# 32_ch_sample_and_hold_v2.net
KiCad netlist of a schematic drawn in EAGLE
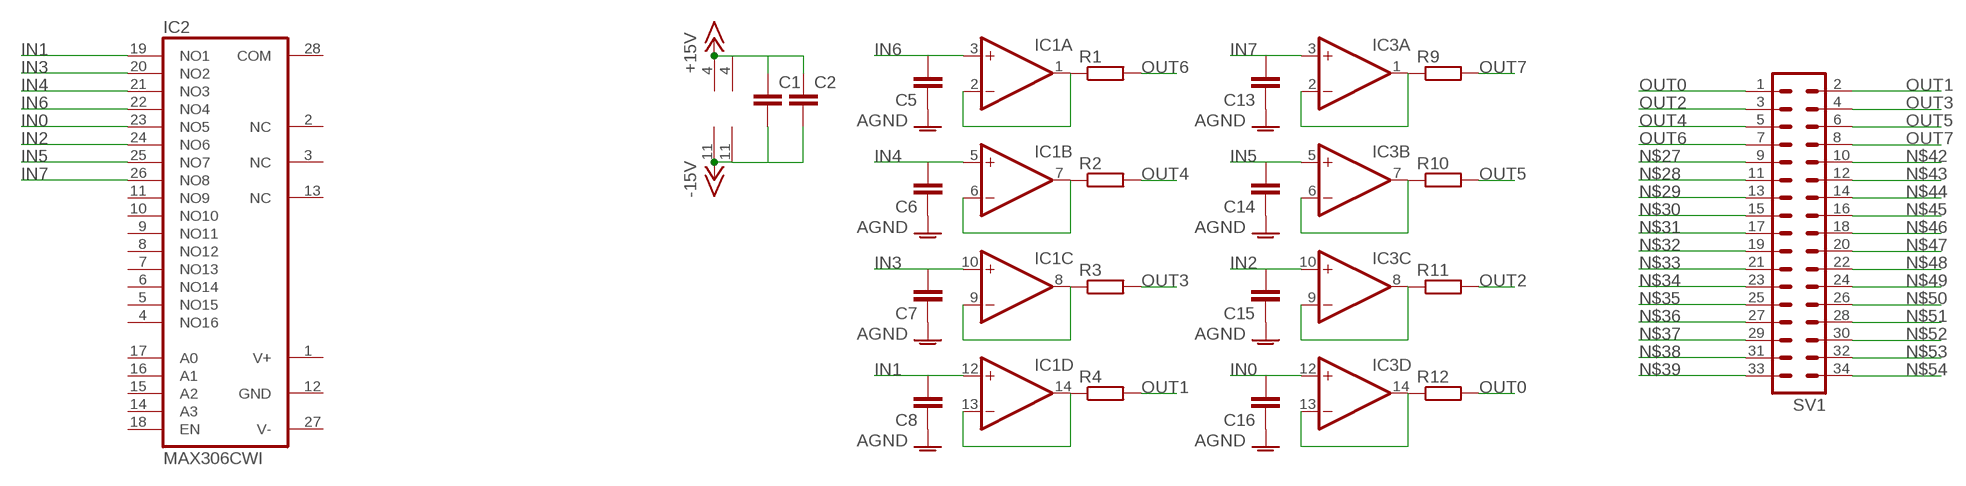
[diagram p0: schematic, sheet 1]

(export (version "E")
  (design (tool "Eeschema 10.0.6"))
  (components
    (comp (ref "C1")
      (value "C-EUC0603")
      (footprint "eagle-import:C0603")
      (libsource (lib "eagle-import") (part "C-EUC0603"))
    )
    (comp (ref "C2")
      (value "C-EUC0603")
      (footprint "eagle-import:C0603")
      (libsource (lib "eagle-import") (part "C-EUC0603"))
    )
    (comp (ref "C5")
      (value "C-EUC1206")
      (footprint "eagle-import:C1206")
      (libsource (lib "eagle-import") (part "C-EUC1206"))
    )
    (comp (ref "C6")
      (value "C-EUC1206")
      (footprint "eagle-import:C1206")
      (libsource (lib "eagle-import") (part "C-EUC1206"))
    )
    (comp (ref "C7")
      (value "C-EUC1206")
      (footprint "eagle-import:C1206")
      (libsource (lib "eagle-import") (part "C-EUC1206"))
    )
    (comp (ref "C8")
      (value "C-EUC1206")
      (footprint "eagle-import:C1206")
      (libsource (lib "eagle-import") (part "C-EUC1206"))
    )
    (comp (ref "C13")
      (value "C-EUC1206")
      (footprint "eagle-import:C1206")
      (libsource (lib "eagle-import") (part "C-EUC1206"))
    )
    (comp (ref "C14")
      (value "C-EUC1206")
      (footprint "eagle-import:C1206")
      (libsource (lib "eagle-import") (part "C-EUC1206"))
    )
    (comp (ref "C15")
      (value "C-EUC1206")
      (footprint "eagle-import:C1206")
      (libsource (lib "eagle-import") (part "C-EUC1206"))
    )
    (comp (ref "C16")
      (value "C-EUC1206")
      (footprint "eagle-import:C1206")
      (libsource (lib "eagle-import") (part "C-EUC1206"))
    )
    (comp (ref "IC1")
      (value "TL074D")
      (footprint "eagle-import:SO14")
      (libsource (lib "eagle-import") (part "TL074D"))
    )
    (comp (ref "IC2")
      (value "MAX306CWI")
      (footprint "eagle-import:SO28L")
      (fields (field (name "MF") "MAXIM"))
      (libsource (lib "eagle-import") (part "MAX306CWI"))
    )
    (comp (ref "IC3")
      (value "TL074D")
      (footprint "eagle-import:SO14")
      (libsource (lib "eagle-import") (part "TL074D"))
    )
    (comp (ref "R1")
      (value "R-EU_R0603")
      (footprint "eagle-import:R0603")
      (libsource (lib "eagle-import") (part "R-EU_R0603"))
    )
    (comp (ref "R2")
      (value "R-EU_R0603")
      (footprint "eagle-import:R0603")
      (libsource (lib "eagle-import") (part "R-EU_R0603"))
    )
    (comp (ref "R3")
      (value "R-EU_R0603")
      (footprint "eagle-import:R0603")
      (libsource (lib "eagle-import") (part "R-EU_R0603"))
    )
    (comp (ref "R4")
      (value "R-EU_R0603")
      (footprint "eagle-import:R0603")
      (libsource (lib "eagle-import") (part "R-EU_R0603"))
    )
    (comp (ref "R9")
      (value "R-EU_R0603")
      (footprint "eagle-import:R0603")
      (libsource (lib "eagle-import") (part "R-EU_R0603"))
    )
    (comp (ref "R10")
      (value "R-EU_R0603")
      (footprint "eagle-import:R0603")
      (libsource (lib "eagle-import") (part "R-EU_R0603"))
    )
    (comp (ref "R11")
      (value "R-EU_R0603")
      (footprint "eagle-import:R0603")
      (libsource (lib "eagle-import") (part "R-EU_R0603"))
    )
    (comp (ref "R12")
      (value "R-EU_R0603")
      (footprint "eagle-import:R0603")
      (libsource (lib "eagle-import") (part "R-EU_R0603"))
    )
    (comp (ref "SV1")
      (value "MA17-2")
      (footprint "eagle-import:MA17-2")
      (libsource (lib "eagle-import") (part "MA17-2"))
    )
  )
  (nets
    (net (code "1") (name "+15V") (class "Default")
      (node (ref "C1") (pin "1") (pinfunction "1_1") (pintype "passive"))
      (node (ref "C2") (pin "1") (pinfunction "1_1") (pintype "passive"))
      (node (ref "IC1") (pin "4") (pinfunction "V+_4") (pintype "power_in"))
      (node (ref "IC3") (pin "4") (pinfunction "V+_4") (pintype "power_in"))
    )
    (net (code "2") (name "-15V") (class "Default")
      (node (ref "C1") (pin "2") (pinfunction "2_2") (pintype "passive"))
      (node (ref "C2") (pin "2") (pinfunction "2_2") (pintype "passive"))
      (node (ref "IC1") (pin "11") (pinfunction "V-_11") (pintype "power_in"))
      (node (ref "IC3") (pin "11") (pinfunction "V-_11") (pintype "power_in"))
    )
    (net (code "3") (name "/GND") (class "Default")
      (node (ref "IC2") (pin "12") (pinfunction "GND_12") (pintype "power_in"))
    )
    (net (code "4") (name "/IN0") (class "Default")
      (node (ref "C16") (pin "2") (pinfunction "2_2") (pintype "passive"))
      (node (ref "IC2") (pin "23") (pinfunction "NO5_23") (pintype "passive"))
      (node (ref "IC3") (pin "12") (pinfunction "+IN_12") (pintype "input"))
    )
    (net (code "5") (name "/IN1") (class "Default")
      (node (ref "C8") (pin "2") (pinfunction "2_2") (pintype "passive"))
      (node (ref "IC1") (pin "12") (pinfunction "+IN_12") (pintype "input"))
      (node (ref "IC2") (pin "19") (pinfunction "NO1_19") (pintype "passive"))
    )
    (net (code "6") (name "/IN2") (class "Default")
      (node (ref "C15") (pin "2") (pinfunction "2_2") (pintype "passive"))
      (node (ref "IC2") (pin "24") (pinfunction "NO6_24") (pintype "passive"))
      (node (ref "IC3") (pin "10") (pinfunction "+IN_10") (pintype "input"))
    )
    (net (code "7") (name "/IN3") (class "Default")
      (node (ref "C7") (pin "2") (pinfunction "2_2") (pintype "passive"))
      (node (ref "IC1") (pin "10") (pinfunction "+IN_10") (pintype "input"))
      (node (ref "IC2") (pin "20") (pinfunction "NO2_20") (pintype "passive"))
    )
    (net (code "8") (name "/IN4") (class "Default")
      (node (ref "C6") (pin "2") (pinfunction "2_2") (pintype "passive"))
      (node (ref "IC1") (pin "5") (pinfunction "+IN_5") (pintype "input"))
      (node (ref "IC2") (pin "21") (pinfunction "NO3_21") (pintype "passive"))
    )
    (net (code "9") (name "/IN5") (class "Default")
      (node (ref "C14") (pin "2") (pinfunction "2_2") (pintype "passive"))
      (node (ref "IC2") (pin "25") (pinfunction "NO7_25") (pintype "passive"))
      (node (ref "IC3") (pin "5") (pinfunction "+IN_5") (pintype "input"))
    )
    (net (code "10") (name "/IN6") (class "Default")
      (node (ref "C5") (pin "2") (pinfunction "2_2") (pintype "passive"))
      (node (ref "IC1") (pin "3") (pinfunction "+IN_3") (pintype "input"))
      (node (ref "IC2") (pin "22") (pinfunction "NO4_22") (pintype "passive"))
    )
    (net (code "11") (name "/IN7") (class "Default")
      (node (ref "C13") (pin "2") (pinfunction "2_2") (pintype "passive"))
      (node (ref "IC2") (pin "26") (pinfunction "NO8_26") (pintype "passive"))
      (node (ref "IC3") (pin "3") (pinfunction "+IN_3") (pintype "input"))
    )
    (net (code "12") (name "/N$27") (class "Default")
      (node (ref "SV1") (pin "9") (pinfunction "9_9") (pintype "passive"))
    )
    (net (code "13") (name "/N$28") (class "Default")
      (node (ref "SV1") (pin "11") (pinfunction "11_11") (pintype "passive"))
    )
    (net (code "14") (name "/N$29") (class "Default")
      (node (ref "SV1") (pin "13") (pinfunction "13_13") (pintype "passive"))
    )
    (net (code "15") (name "/N$30") (class "Default")
      (node (ref "SV1") (pin "15") (pinfunction "15_15") (pintype "passive"))
    )
    (net (code "16") (name "/N$31") (class "Default")
      (node (ref "SV1") (pin "17") (pinfunction "17_17") (pintype "passive"))
    )
    (net (code "17") (name "/N$32") (class "Default")
      (node (ref "SV1") (pin "19") (pinfunction "19_19") (pintype "passive"))
    )
    (net (code "18") (name "/N$33") (class "Default")
      (node (ref "SV1") (pin "21") (pinfunction "21_21") (pintype "passive"))
    )
    (net (code "19") (name "/N$34") (class "Default")
      (node (ref "SV1") (pin "23") (pinfunction "23_23") (pintype "passive"))
    )
    (net (code "20") (name "/N$35") (class "Default")
      (node (ref "SV1") (pin "25") (pinfunction "25_25") (pintype "passive"))
    )
    (net (code "21") (name "/N$36") (class "Default")
      (node (ref "SV1") (pin "27") (pinfunction "27_27") (pintype "passive"))
    )
    (net (code "22") (name "/N$37") (class "Default")
      (node (ref "SV1") (pin "29") (pinfunction "29_29") (pintype "passive"))
    )
    (net (code "23") (name "/N$38") (class "Default")
      (node (ref "SV1") (pin "31") (pinfunction "31_31") (pintype "passive"))
    )
    (net (code "24") (name "/N$39") (class "Default")
      (node (ref "SV1") (pin "33") (pinfunction "33_33") (pintype "passive"))
    )
    (net (code "25") (name "/N$42") (class "Default")
      (node (ref "SV1") (pin "10") (pinfunction "10_10") (pintype "passive"))
    )
    (net (code "26") (name "/N$43") (class "Default")
      (node (ref "SV1") (pin "12") (pinfunction "12_12") (pintype "passive"))
    )
    (net (code "27") (name "/N$44") (class "Default")
      (node (ref "SV1") (pin "14") (pinfunction "14_14") (pintype "passive"))
    )
    (net (code "28") (name "/N$45") (class "Default")
      (node (ref "SV1") (pin "16") (pinfunction "16_16") (pintype "passive"))
    )
    (net (code "29") (name "/N$46") (class "Default")
      (node (ref "SV1") (pin "18") (pinfunction "18_18") (pintype "passive"))
    )
    (net (code "30") (name "/N$47") (class "Default")
      (node (ref "SV1") (pin "20") (pinfunction "20_20") (pintype "passive"))
    )
    (net (code "31") (name "/N$48") (class "Default")
      (node (ref "SV1") (pin "22") (pinfunction "22_22") (pintype "passive"))
    )
    (net (code "32") (name "/N$49") (class "Default")
      (node (ref "SV1") (pin "24") (pinfunction "24_24") (pintype "passive"))
    )
    (net (code "33") (name "/N$50") (class "Default")
      (node (ref "SV1") (pin "26") (pinfunction "26_26") (pintype "passive"))
    )
    (net (code "34") (name "/N$51") (class "Default")
      (node (ref "SV1") (pin "28") (pinfunction "28_28") (pintype "passive"))
    )
    (net (code "35") (name "/N$52") (class "Default")
      (node (ref "SV1") (pin "30") (pinfunction "30_30") (pintype "passive"))
    )
    (net (code "36") (name "/N$53") (class "Default")
      (node (ref "SV1") (pin "32") (pinfunction "32_32") (pintype "passive"))
    )
    (net (code "37") (name "/N$54") (class "Default")
      (node (ref "SV1") (pin "34") (pinfunction "34_34") (pintype "passive"))
    )
    (net (code "38") (name "/OUT0") (class "Default")
      (node (ref "R12") (pin "2") (pinfunction "2_2") (pintype "passive"))
      (node (ref "SV1") (pin "1") (pinfunction "1_1") (pintype "passive"))
    )
    (net (code "39") (name "/OUT1") (class "Default")
      (node (ref "R4") (pin "2") (pinfunction "2_2") (pintype "passive"))
      (node (ref "SV1") (pin "2") (pinfunction "2_2") (pintype "passive"))
    )
    (net (code "40") (name "/OUT2") (class "Default")
      (node (ref "R11") (pin "2") (pinfunction "2_2") (pintype "passive"))
      (node (ref "SV1") (pin "3") (pinfunction "3_3") (pintype "passive"))
    )
    (net (code "41") (name "/OUT3") (class "Default")
      (node (ref "R3") (pin "2") (pinfunction "2_2") (pintype "passive"))
      (node (ref "SV1") (pin "4") (pinfunction "4_4") (pintype "passive"))
    )
    (net (code "42") (name "/OUT4") (class "Default")
      (node (ref "R2") (pin "2") (pinfunction "2_2") (pintype "passive"))
      (node (ref "SV1") (pin "5") (pinfunction "5_5") (pintype "passive"))
    )
    (net (code "43") (name "/OUT5") (class "Default")
      (node (ref "R10") (pin "2") (pinfunction "2_2") (pintype "passive"))
      (node (ref "SV1") (pin "6") (pinfunction "6_6") (pintype "passive"))
    )
    (net (code "44") (name "/OUT6") (class "Default")
      (node (ref "R1") (pin "2") (pinfunction "2_2") (pintype "passive"))
      (node (ref "SV1") (pin "7") (pinfunction "7_7") (pintype "passive"))
    )
    (net (code "45") (name "/OUT7") (class "Default")
      (node (ref "R9") (pin "2") (pinfunction "2_2") (pintype "passive"))
      (node (ref "SV1") (pin "8") (pinfunction "8_8") (pintype "passive"))
    )
    (net (code "46") (name "/V+") (class "Default")
      (node (ref "IC2") (pin "1") (pinfunction "V+_1") (pintype "power_in"))
    )
    (net (code "47") (name "/V-") (class "Default")
      (node (ref "IC2") (pin "27") (pinfunction "V-_27") (pintype "power_in"))
    )
    (net (code "48") (name "AGND") (class "Default")
      (node (ref "C13") (pin "1") (pinfunction "1_1") (pintype "passive"))
      (node (ref "C14") (pin "1") (pinfunction "1_1") (pintype "passive"))
      (node (ref "C15") (pin "1") (pinfunction "1_1") (pintype "passive"))
      (node (ref "C16") (pin "1") (pinfunction "1_1") (pintype "passive"))
      (node (ref "C5") (pin "1") (pinfunction "1_1") (pintype "passive"))
      (node (ref "C6") (pin "1") (pinfunction "1_1") (pintype "passive"))
      (node (ref "C7") (pin "1") (pinfunction "1_1") (pintype "passive"))
      (node (ref "C8") (pin "1") (pinfunction "1_1") (pintype "passive"))
    )
    (net (code "49") (name "Net-(IC1A--IN)") (class "Default")
      (node (ref "IC1") (pin "1") (pinfunction "OUT_1") (pintype "output"))
      (node (ref "IC1") (pin "2") (pinfunction "-IN_2") (pintype "input"))
      (node (ref "R1") (pin "1") (pinfunction "1_1") (pintype "passive"))
    )
    (net (code "50") (name "Net-(IC1B--IN)") (class "Default")
      (node (ref "IC1") (pin "6") (pinfunction "-IN_6") (pintype "input"))
      (node (ref "IC1") (pin "7") (pinfunction "OUT_7") (pintype "output"))
      (node (ref "R2") (pin "1") (pinfunction "1_1") (pintype "passive"))
    )
    (net (code "51") (name "Net-(IC1C--IN)") (class "Default")
      (node (ref "IC1") (pin "8") (pinfunction "OUT_8") (pintype "output"))
      (node (ref "IC1") (pin "9") (pinfunction "-IN_9") (pintype "input"))
      (node (ref "R3") (pin "1") (pinfunction "1_1") (pintype "passive"))
    )
    (net (code "52") (name "Net-(IC1D--IN)") (class "Default")
      (node (ref "IC1") (pin "13") (pinfunction "-IN_13") (pintype "input"))
      (node (ref "IC1") (pin "14") (pinfunction "OUT_14") (pintype "output"))
      (node (ref "R4") (pin "1") (pinfunction "1_1") (pintype "passive"))
    )
    (net (code "53") (name "Net-(IC3A--IN)") (class "Default")
      (node (ref "IC3") (pin "1") (pinfunction "OUT_1") (pintype "output"))
      (node (ref "IC3") (pin "2") (pinfunction "-IN_2") (pintype "input"))
      (node (ref "R9") (pin "1") (pinfunction "1_1") (pintype "passive"))
    )
    (net (code "54") (name "Net-(IC3B--IN)") (class "Default")
      (node (ref "IC3") (pin "6") (pinfunction "-IN_6") (pintype "input"))
      (node (ref "IC3") (pin "7") (pinfunction "OUT_7") (pintype "output"))
      (node (ref "R10") (pin "1") (pinfunction "1_1") (pintype "passive"))
    )
    (net (code "55") (name "Net-(IC3C--IN)") (class "Default")
      (node (ref "IC3") (pin "8") (pinfunction "OUT_8") (pintype "output"))
      (node (ref "IC3") (pin "9") (pinfunction "-IN_9") (pintype "input"))
      (node (ref "R11") (pin "1") (pinfunction "1_1") (pintype "passive"))
    )
    (net (code "56") (name "Net-(IC3D--IN)") (class "Default")
      (node (ref "IC3") (pin "13") (pinfunction "-IN_13") (pintype "input"))
      (node (ref "IC3") (pin "14") (pinfunction "OUT_14") (pintype "output"))
      (node (ref "R12") (pin "1") (pinfunction "1_1") (pintype "passive"))
    )
    (net (code "57") (name "unconnected-(IC2-A0-Pad17)") (class "Default")
      (node (ref "IC2") (pin "17") (pinfunction "A0_17") (pintype "input"))
    )
    (net (code "58") (name "unconnected-(IC2-A1-Pad16)") (class "Default")
      (node (ref "IC2") (pin "16") (pinfunction "A1_16") (pintype "input"))
    )
    (net (code "59") (name "unconnected-(IC2-A2-Pad15)") (class "Default")
      (node (ref "IC2") (pin "15") (pinfunction "A2_15") (pintype "input"))
    )
    (net (code "60") (name "unconnected-(IC2-A3-Pad14)") (class "Default")
      (node (ref "IC2") (pin "14") (pinfunction "A3_14") (pintype "input"))
    )
    (net (code "61") (name "unconnected-(IC2-COM-Pad28)") (class "Default")
      (node (ref "IC2") (pin "28") (pinfunction "COM_28") (pintype "passive"))
    )
    (net (code "62") (name "unconnected-(IC2-EN-Pad18)") (class "Default")
      (node (ref "IC2") (pin "18") (pinfunction "EN_18") (pintype "input"))
    )
    (net (code "63") (name "unconnected-(IC2-NC-Pad2)") (class "Default")
      (node (ref "IC2") (pin "2") (pinfunction "NC_2") (pintype "no_connect"))
    )
    (net (code "64") (name "unconnected-(IC2-NC-Pad3)") (class "Default")
      (node (ref "IC2") (pin "3") (pinfunction "NC_3") (pintype "no_connect"))
    )
    (net (code "65") (name "unconnected-(IC2-NC-Pad13)") (class "Default")
      (node (ref "IC2") (pin "13") (pinfunction "NC_13") (pintype "no_connect"))
    )
    (net (code "66") (name "unconnected-(IC2-NO9-Pad11)") (class "Default")
      (node (ref "IC2") (pin "11") (pinfunction "NO9_11") (pintype "passive"))
    )
    (net (code "67") (name "unconnected-(IC2-NO10-Pad10)") (class "Default")
      (node (ref "IC2") (pin "10") (pinfunction "NO10_10") (pintype "passive"))
    )
    (net (code "68") (name "unconnected-(IC2-NO11-Pad9)") (class "Default")
      (node (ref "IC2") (pin "9") (pinfunction "NO11_9") (pintype "passive"))
    )
    (net (code "69") (name "unconnected-(IC2-NO12-Pad8)") (class "Default")
      (node (ref "IC2") (pin "8") (pinfunction "NO12_8") (pintype "passive"))
    )
    (net (code "70") (name "unconnected-(IC2-NO13-Pad7)") (class "Default")
      (node (ref "IC2") (pin "7") (pinfunction "NO13_7") (pintype "passive"))
    )
    (net (code "71") (name "unconnected-(IC2-NO14-Pad6)") (class "Default")
      (node (ref "IC2") (pin "6") (pinfunction "NO14_6") (pintype "passive"))
    )
    (net (code "72") (name "unconnected-(IC2-NO15-Pad5)") (class "Default")
      (node (ref "IC2") (pin "5") (pinfunction "NO15_5") (pintype "passive"))
    )
    (net (code "73") (name "unconnected-(IC2-NO16-Pad4)") (class "Default")
      (node (ref "IC2") (pin "4") (pinfunction "NO16_4") (pintype "passive"))
    )
  )
)
